# Motor_Controller.net
KiCad netlist of a schematic drawn in Altium Designer
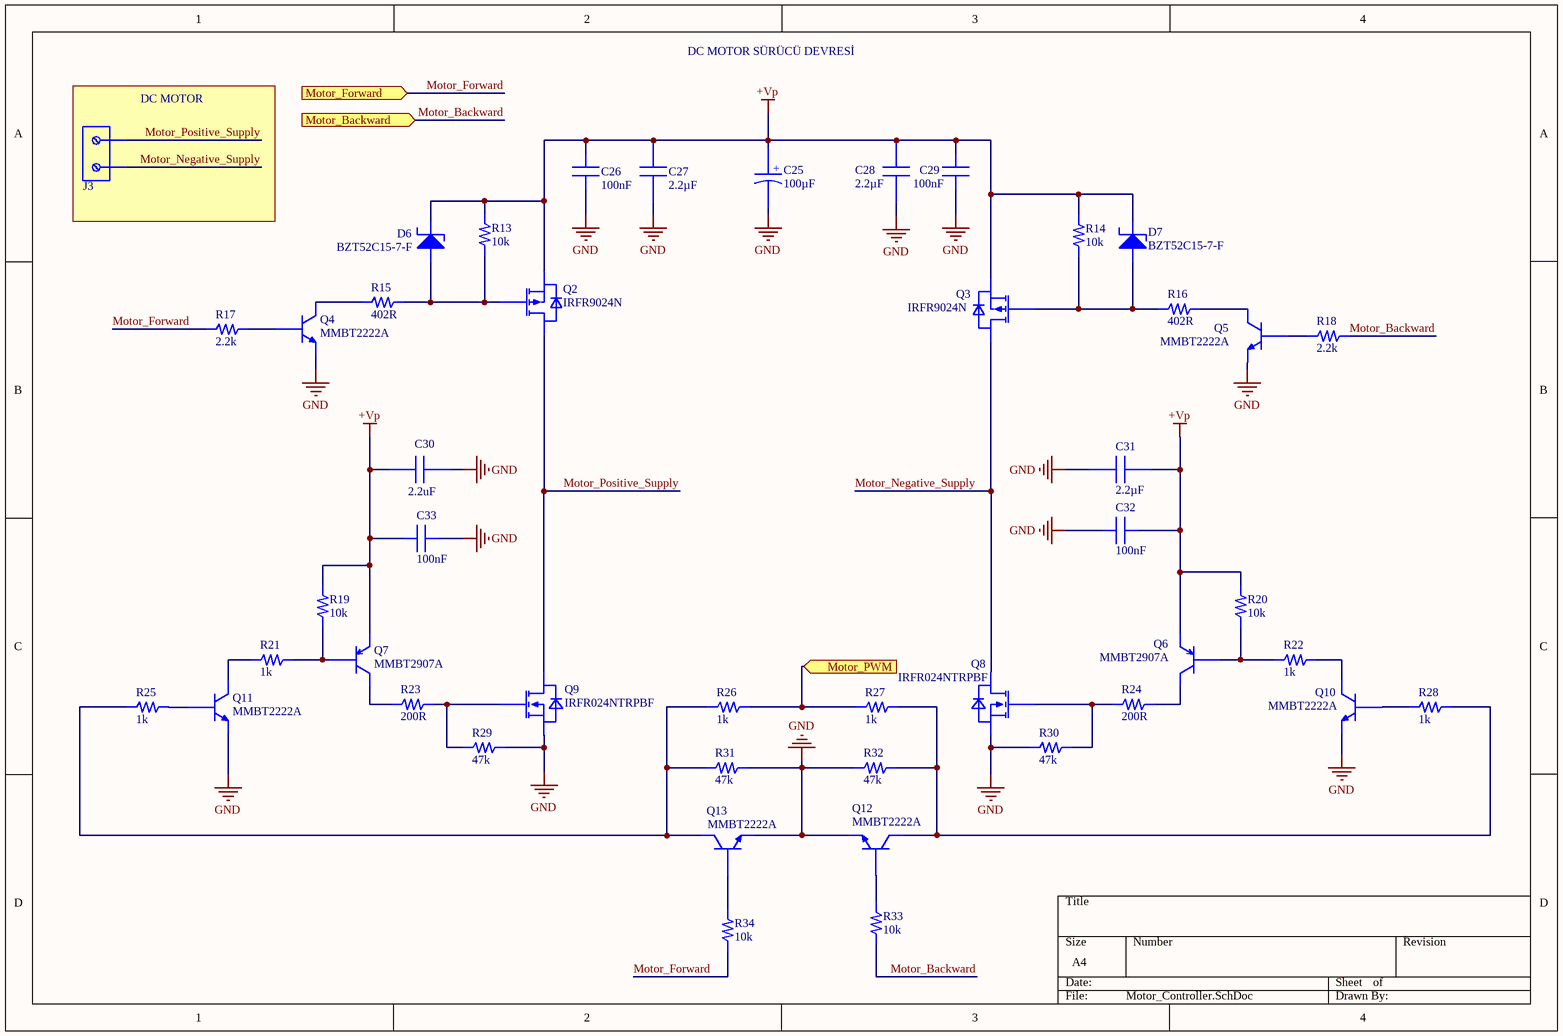
[diagram p0: Motor_Controller.SchDoc]

(export (version "E")
  (design (tool "Eeschema 10.0.6"))
  (components
    (comp (ref "C25")
      (value "100µF")
      (footprint "CAP_EEHZA1H101P")
      (description "CAP.EL.100µF 50V 10.5x10.5 105C SMD")
      (fields (field (name "MANUFACTURER") "Panasonic") (field (name "TOLERANCE") "±20 %"))
      (libsource (lib "Motor Controller SchLib") (part "CAP 100uF"))
    )
    (comp (ref "C26")
      (value "100nF")
      (footprint "CL21B104KBCNNNC")
      (description "MLCC 0805 100nF 50VDC ±10% X7R")
      (fields (field (name "TOLERANCE") "±10 %") (field (name "MANUFACTURER") "SAMSUNG"))
      (libsource (lib "Motor Controller SchLib") (part "CAP 0805 100nF"))
    )
    (comp (ref "C27")
      (value "2.2µF")
      (footprint "CAPC3216X180N")
      (description "MLCC 1206 2.2µF 50VDC ±10% X7R")
      (fields (field (name "MANUFACTURER") "SAMSUNG") (field (name "TOLERANCE") "±10 %"))
      (libsource (lib "Motor Controller SchLib") (part "CAP 1206 2.2uF"))
    )
    (comp (ref "C28")
      (value "2.2µF")
      (footprint "CAPC3216X180N")
      (description "MLCC 1206 2.2µF 50VDC ±10% X7R")
      (fields (field (name "MANUFACTURER") "SAMSUNG") (field (name "TOLERANCE") "±10 %"))
      (libsource (lib "Motor Controller SchLib") (part "CAP 1206 2.2uF"))
    )
    (comp (ref "C29")
      (value "100nF")
      (footprint "CL21B104KBCNNNC")
      (description "MLCC 0805 100nF 50VDC ±10% X7R")
      (fields (field (name "TOLERANCE") "±10 %") (field (name "MANUFACTURER") "SAMSUNG"))
      (libsource (lib "Motor Controller SchLib") (part "CAP 0805 100nF"))
    )
    (comp (ref "C30")
      (value "2.2µF")
      (footprint "CAPC3216X180N")
      (description "MLCC 1206 2.2µF 50VDC ±10% X7R")
      (fields (field (name "MANUFACTURER") "SAMSUNG") (field (name "TOLERANCE") "±10 %"))
      (libsource (lib "Motor Controller SchLib") (part "CAP 1206 2.2uF"))
    )
    (comp (ref "C31")
      (value "2.2µF")
      (footprint "CAPC3216X180N")
      (description "MLCC 1206 2.2µF 50VDC ±10% X7R")
      (fields (field (name "MANUFACTURER") "SAMSUNG") (field (name "TOLERANCE") "±10 %"))
      (libsource (lib "Motor Controller SchLib") (part "CAP 1206 2.2uF"))
    )
    (comp (ref "C32")
      (value "100nF")
      (footprint "CL21B104KBCNNNC")
      (description "MLCC 0805 100nF 50VDC ±10% X7R")
      (fields (field (name "TOLERANCE") "±10 %") (field (name "MANUFACTURER") "SAMSUNG"))
      (libsource (lib "Motor Controller SchLib") (part "CAP 0805 100nF"))
    )
    (comp (ref "C33")
      (value "100nF")
      (footprint "CL21B104KBCNNNC")
      (description "MLCC 0805 100nF 50VDC ±10% X7R")
      (fields (field (name "TOLERANCE") "±10 %") (field (name "MANUFACTURER") "SAMSUNG"))
      (libsource (lib "Motor Controller SchLib") (part "CAP 0805 100nF"))
    )
    (comp (ref "D6")
      (value "BZT52C15-7-F")
      (footprint "DIODE ZENER BZT52C15-7-F")
      (description "DIODE ZENER 500mW 15V ±5% SOD123 SMT")
      (fields (field (name "TOLERANCE") "±5 %") (field (name "POWER") "500 mW"))
      (libsource (lib "Motor Controller SchLib") (part "DIODE ZENER 15V BZT52C15-7-F"))
    )
    (comp (ref "D7")
      (value "BZT52C15-7-F")
      (footprint "DIODE ZENER BZT52C15-7-F")
      (description "DIODE ZENER 500mW 15V ±5% SOD123 SMT")
      (fields (field (name "TOLERANCE") "±5 %") (field (name "POWER") "500 mW"))
      (libsource (lib "Motor Controller SchLib") (part "DIODE ZENER 15V BZT52C15-7-F"))
    )
    (comp (ref "J3")
      (value "2x1 5mm T.B.")
      (footprint "Terminal Block 2x1")
      (description "TERM.BLK.5.00MM 2P PCB TYPE 0 BOY BLUE")
      (fields (field (name "MANUFACTURER") "DEGSON"))
      (libsource (lib "Motor Controller SchLib") (part "Terminal Block 2x1"))
    )
    (comp (ref "Q2")
      (value "IRFR9024N")
      (footprint "TO252 (DPAK) IRFR024NTRPBF")
      (description "MOSFET DIS.11A 55V P-CH TO252(DPAK) HEXFET SMT")
      (fields (field (name "POWER") "38 W") (field (name "VOLTAGE") "55 V"))
      (libsource (lib "Motor Controller SchLib") (part "P Channel Mosfet IRFR9024N"))
    )
    (comp (ref "Q3")
      (value "IRFR9024N")
      (footprint "TO252 (DPAK) IRFR024NTRPBF")
      (description "MOSFET DIS.11A 55V P-CH TO252(DPAK) HEXFET SMT")
      (fields (field (name "POWER") "38 W") (field (name "VOLTAGE") "55 V"))
      (libsource (lib "Motor Controller SchLib") (part "P Channel Mosfet IRFR9024N"))
    )
    (comp (ref "Q4")
      (value "MMBT2222A")
      (footprint "SOT23-3 MMBT2222A-HT")
      (description "TRANSISTOR DIS.600mA 40V NPN SOT23 EPITAXIAL SMT")
      (fields (field (name "MANUFACTURER") "HOTTECH") (field (name "POWER") "250 mW"))
      (libsource (lib "Motor Controller SchLib") (part "NPN Transistor MMBT2222A-HT"))
    )
    (comp (ref "Q5")
      (value "MMBT2222A")
      (footprint "SOT23-3 MMBT2222A-HT")
      (description "TRANSISTOR DIS.600mA 40V NPN SOT23 EPITAXIAL SMT")
      (fields (field (name "MANUFACTURER") "HOTTECH") (field (name "POWER") "250 mW"))
      (libsource (lib "Motor Controller SchLib") (part "NPN Transistor MMBT2222A-HT"))
    )
    (comp (ref "Q6")
      (value "MMBT2907A")
      (footprint "TRANS_MMBT2907A")
      (description "TRANSISTOR DIS.600mA 60V PNP SOT23 GEN. SMT")
      (fields (field (name "MANUFACTURER") "PANJIT") (field (name "POWER") "225 mW"))
      (libsource (lib "Motor Controller SchLib") (part "PNP Transistor MMBT2907A"))
    )
    (comp (ref "Q7")
      (value "MMBT2907A")
      (footprint "TRANS_MMBT2907A")
      (description "TRANSISTOR DIS.600mA 60V PNP SOT23 GEN. SMT")
      (fields (field (name "MANUFACTURER") "PANJIT") (field (name "POWER") "225 mW"))
      (libsource (lib "Motor Controller SchLib") (part "PNP Transistor MMBT2907A"))
    )
    (comp (ref "Q8")
      (value "IRFR024NTRPBF")
      (footprint "TO252 (DPAK) IRFR024NTRPBF")
      (description "MOSFET DIS.17A 55V N-CH TO252(DPAK) HEXFET SMT")
      (fields (field (name "VOLTAGE") "55 V") (field (name "POWER") "45W"))
      (libsource (lib "Motor Controller SchLib") (part "N Channel Mosfet IRFR024NTRPBF"))
    )
    (comp (ref "Q9")
      (value "IRFR024NTRPBF")
      (footprint "TO252 (DPAK) IRFR024NTRPBF")
      (description "MOSFET DIS.17A 55V N-CH TO252(DPAK) HEXFET SMT")
      (fields (field (name "VOLTAGE") "55 V") (field (name "POWER") "45W"))
      (libsource (lib "Motor Controller SchLib") (part "N Channel Mosfet IRFR024NTRPBF"))
    )
    (comp (ref "Q10")
      (value "MMBT2222A")
      (footprint "SOT23-3 MMBT2222A-HT")
      (description "TRANSISTOR DIS.600mA 40V NPN SOT23 EPITAXIAL SMT")
      (fields (field (name "MANUFACTURER") "HOTTECH") (field (name "POWER") "250 mW"))
      (libsource (lib "Motor Controller SchLib") (part "NPN Transistor MMBT2222A-HT"))
    )
    (comp (ref "Q11")
      (value "MMBT2222A")
      (footprint "SOT23-3 MMBT2222A-HT")
      (description "TRANSISTOR DIS.600mA 40V NPN SOT23 EPITAXIAL SMT")
      (fields (field (name "MANUFACTURER") "HOTTECH") (field (name "POWER") "250 mW"))
      (libsource (lib "Motor Controller SchLib") (part "NPN Transistor MMBT2222A-HT"))
    )
    (comp (ref "Q12")
      (value "MMBT2222A")
      (footprint "SOT23-3 MMBT2222A-HT")
      (description "TRANSISTOR DIS.600mA 40V NPN SOT23 EPITAXIAL SMT")
      (fields (field (name "POWER") "250 mW") (field (name "MANUFACTURER") "HOTTECH"))
      (libsource (lib "Motor Controller SchLib") (part "NPN Transistor MMBT2222A-HT"))
    )
    (comp (ref "Q13")
      (value "MMBT2222A")
      (footprint "SOT23-3 MMBT2222A-HT")
      (description "TRANSISTOR DIS.600mA 40V NPN SOT23 EPITAXIAL SMT")
      (fields (field (name "POWER") "250 mW") (field (name "MANUFACTURER") "HOTTECH"))
      (libsource (lib "Motor Controller SchLib") (part "NPN Transistor MMBT2222A-HT"))
    )
    (comp (ref "R13")
      (value "10k")
      (footprint "RES 0402 ROYALOHM GENERAL")
      (description "RES.(1005) 0402 10K Ohms 5% 1/16W 100PPM 0402WGJ0103TCE")
      (fields (field (name "TOLERANCE") "%5") (field (name "MANUFACTURER") "ROYALOHM"))
      (libsource (lib "Motor Controller SchLib") (part "RES 0402 10k"))
    )
    (comp (ref "R14")
      (value "10k")
      (footprint "RES 0402 ROYALOHM GENERAL")
      (description "RES.(1005) 0402 10K Ohms 5% 1/16W 100PPM 0402WGJ0103TCE")
      (fields (field (name "TOLERANCE") "%5") (field (name "MANUFACTURER") "ROYALOHM"))
      (libsource (lib "Motor Controller SchLib") (part "RES 0402 10k"))
    )
    (comp (ref "R15")
      (value "402R")
      (footprint "CHIP RES 0805 1k")
      (description "RES.(2012) 0805 402 Ohms 1% 1/8W-S 100PPM 0805S8F4020T5E")
      (fields (field (name "MANUFACTURER") "ROYALOHM") (field (name "TOLERANCE") "±1 %"))
      (libsource (lib "Motor Controller SchLib") (part "RES 0805 402 Ohms 0402WGF4020TCE"))
    )
    (comp (ref "R16")
      (value "402R")
      (footprint "CHIP RES 0805 1k")
      (description "RES.(2012) 0805 402 Ohms 1% 1/8W-S 100PPM 0805S8F4020T5E")
      (fields (field (name "MANUFACTURER") "ROYALOHM") (field (name "TOLERANCE") "±1 %"))
      (libsource (lib "Motor Controller SchLib") (part "RES 0805 402 Ohms 0402WGF4020TCE"))
    )
    (comp (ref "R17")
      (value "2.2k")
      (footprint "RES 0402 ROYALOHM GENERAL")
      (description "RES. 0805 2.2k Ohms 1% 1/8W-S 100PPM 0402WGF2201TCE")
      (fields (field (name "TOLERANCE") "%1") (field (name "POWER") "1/16 W"))
      (libsource (lib "Motor Controller SchLib") (part "RES 0402 2.2k 0402WGF2201TCE"))
    )
    (comp (ref "R18")
      (value "2.2k")
      (footprint "RES 0402 ROYALOHM GENERAL")
      (description "RES. 0805 2.2k Ohms 1% 1/8W-S 100PPM 0402WGF2201TCE")
      (fields (field (name "TOLERANCE") "%1") (field (name "POWER") "1/16 W"))
      (libsource (lib "Motor Controller SchLib") (part "RES 0402 2.2k 0402WGF2201TCE"))
    )
    (comp (ref "R19")
      (value "10k")
      (footprint "RES 0402 ROYALOHM GENERAL")
      (description "RES.(1005) 0402 10K Ohms 5% 1/16W 100PPM 0402WGJ0103TCE")
      (fields (field (name "TOLERANCE") "%5") (field (name "MANUFACTURER") "ROYALOHM"))
      (libsource (lib "Motor Controller SchLib") (part "RES 0402 10k"))
    )
    (comp (ref "R20")
      (value "10k")
      (footprint "RES 0402 ROYALOHM GENERAL")
      (description "RES.(1005) 0402 10K Ohms 5% 1/16W 100PPM 0402WGJ0103TCE")
      (fields (field (name "TOLERANCE") "%5") (field (name "MANUFACTURER") "ROYALOHM"))
      (libsource (lib "Motor Controller SchLib") (part "RES 0402 10k"))
    )
    (comp (ref "R21")
      (value "1k")
      (footprint "RES 0402 ROYALOHM GENERAL")
      (description "RES.(1005) 0402 1K Ohms 1% 1/10W\r\nHP02WAF1001TCE")
      (fields (field (name "MANUFACTURER") "ROYALOHM") (field (name "TOLERANCE") "±1 %"))
      (libsource (lib "Motor Controller SchLib") (part "RES 0402 1k HP02WAF1001TCE"))
    )
    (comp (ref "R22")
      (value "1k")
      (footprint "RES 0402 ROYALOHM GENERAL")
      (description "RES.(1005) 0402 1K Ohms 1% 1/10W\r\nHP02WAF1001TCE")
      (fields (field (name "MANUFACTURER") "ROYALOHM") (field (name "TOLERANCE") "±1 %"))
      (libsource (lib "Motor Controller SchLib") (part "RES 0402 1k HP02WAF1001TCE"))
    )
    (comp (ref "R23")
      (value "200R")
      (footprint "CHIP RES 0805 1k")
      (description "RES.(2012) 0805 200 Ohms 5% 1/8W-S 100PPM\r\n0805S8J0201T5E")
      (fields (field (name "TOLERANCE") "±5 %") (field (name "MANUFACTURER") "ROYALOHM"))
      (libsource (lib "Motor Controller SchLib") (part "RES 0805 200Ohms 0805S8J0201T5E"))
    )
    (comp (ref "R24")
      (value "200R")
      (footprint "CHIP RES 0805 1k")
      (description "RES.(2012) 0805 200 Ohms 5% 1/8W-S 100PPM\r\n0805S8J0201T5E")
      (fields (field (name "TOLERANCE") "±5 %") (field (name "MANUFACTURER") "ROYALOHM"))
      (libsource (lib "Motor Controller SchLib") (part "RES 0805 200Ohms 0805S8J0201T5E"))
    )
    (comp (ref "R25")
      (value "1k")
      (footprint "RES 0402 ROYALOHM GENERAL")
      (description "RES.(1005) 0402 1K Ohms 1% 1/10W\r\nHP02WAF1001TCE")
      (fields (field (name "MANUFACTURER") "ROYALOHM") (field (name "TOLERANCE") "±1 %"))
      (libsource (lib "Motor Controller SchLib") (part "RES 0402 1k HP02WAF1001TCE"))
    )
    (comp (ref "R26")
      (value "1k")
      (footprint "RES 0402 ROYALOHM GENERAL")
      (description "RES.(1005) 0402 1K Ohms 1% 1/10W\r\nHP02WAF1001TCE")
      (fields (field (name "MANUFACTURER") "ROYALOHM") (field (name "TOLERANCE") "±1 %"))
      (libsource (lib "Motor Controller SchLib") (part "RES 0402 1k HP02WAF1001TCE"))
    )
    (comp (ref "R27")
      (value "1k")
      (footprint "RES 0402 ROYALOHM GENERAL")
      (description "RES.(1005) 0402 1K Ohms 1% 1/10W\r\nHP02WAF1001TCE")
      (fields (field (name "MANUFACTURER") "ROYALOHM") (field (name "TOLERANCE") "±1 %"))
      (libsource (lib "Motor Controller SchLib") (part "RES 0402 1k HP02WAF1001TCE"))
    )
    (comp (ref "R28")
      (value "1k")
      (footprint "RES 0402 ROYALOHM GENERAL")
      (description "RES.(1005) 0402 1K Ohms 1% 1/10W\r\nHP02WAF1001TCE")
      (fields (field (name "MANUFACTURER") "ROYALOHM") (field (name "TOLERANCE") "±1 %"))
      (libsource (lib "Motor Controller SchLib") (part "RES 0402 1k HP02WAF1001TCE"))
    )
    (comp (ref "R29")
      (value "47k")
      (footprint "RES 0402 ROYALOHM GENERAL")
      (description "RES.(1005) 0402 47K Ohms 1% 1/10W\r\nHP02WAF4702TCE")
      (fields (field (name "TOLERANCE") "±1 %") (field (name "MANUFACTURER") "ROYALOHM"))
      (libsource (lib "Motor Controller SchLib") (part "RES 0402 47k HP02WAF4702TCE"))
    )
    (comp (ref "R30")
      (value "47k")
      (footprint "RES 0402 ROYALOHM GENERAL")
      (description "RES.(1005) 0402 47K Ohms 1% 1/10W\r\nHP02WAF4702TCE")
      (fields (field (name "TOLERANCE") "±1 %") (field (name "MANUFACTURER") "ROYALOHM"))
      (libsource (lib "Motor Controller SchLib") (part "RES 0402 47k HP02WAF4702TCE"))
    )
    (comp (ref "R31")
      (value "47k")
      (footprint "RES 0402 ROYALOHM GENERAL")
      (description "RES.(1005) 0402 47K Ohms 1% 1/10W\r\nHP02WAF4702TCE")
      (fields (field (name "TOLERANCE") "±1 %") (field (name "MANUFACTURER") "ROYALOHM"))
      (libsource (lib "Motor Controller SchLib") (part "RES 0402 47k HP02WAF4702TCE"))
    )
    (comp (ref "R32")
      (value "47k")
      (footprint "RES 0402 ROYALOHM GENERAL")
      (description "RES.(1005) 0402 47K Ohms 1% 1/10W\r\nHP02WAF4702TCE")
      (fields (field (name "TOLERANCE") "±1 %") (field (name "MANUFACTURER") "ROYALOHM"))
      (libsource (lib "Motor Controller SchLib") (part "RES 0402 47k HP02WAF4702TCE"))
    )
    (comp (ref "R33")
      (value "10k")
      (footprint "RES 0402 ROYALOHM GENERAL")
      (description "RES.(1005) 0402 10K Ohms 5% 1/16W 100PPM 0402WGJ0103TCE")
      (fields (field (name "TOLERANCE") "%5") (field (name "MANUFACTURER") "ROYALOHM"))
      (libsource (lib "Motor Controller SchLib") (part "RES 0402 10k"))
    )
    (comp (ref "R34")
      (value "10k")
      (footprint "RES 0402 ROYALOHM GENERAL")
      (description "RES.(1005) 0402 10K Ohms 5% 1/16W 100PPM 0402WGJ0103TCE")
      (fields (field (name "TOLERANCE") "%5") (field (name "MANUFACTURER") "ROYALOHM"))
      (libsource (lib "Motor Controller SchLib") (part "RES 0402 10k"))
    )
  )
  (nets
    (net (code "1") (name "+Vp") (class "Default")
      (node (ref "C25") (pin "1") (pinfunction "1_1") (pintype "passive"))
      (node (ref "C26") (pin "2") (pinfunction "2_2") (pintype "passive"))
      (node (ref "C27") (pin "2") (pinfunction "2_2") (pintype "passive"))
      (node (ref "C28") (pin "2") (pinfunction "2_2") (pintype "passive"))
      (node (ref "C29") (pin "2") (pinfunction "2_2") (pintype "passive"))
      (node (ref "C30") (pin "1") (pinfunction "1_1") (pintype "passive"))
      (node (ref "C31") (pin "2") (pinfunction "2_2") (pintype "passive"))
      (node (ref "C32") (pin "2") (pinfunction "2_2") (pintype "passive"))
      (node (ref "C33") (pin "1") (pinfunction "1_1") (pintype "passive"))
      (node (ref "D6") (pin "2") (pinfunction "Cathode_2") (pintype "passive"))
      (node (ref "D7") (pin "2") (pinfunction "Cathode_2") (pintype "passive"))
      (node (ref "Q2") (pin "3") (pinfunction "Source_3") (pintype "passive"))
      (node (ref "Q3") (pin "3") (pinfunction "Source_3") (pintype "passive"))
      (node (ref "Q6") (pin "2") (pinfunction "Emitter_2") (pintype "passive"))
      (node (ref "Q7") (pin "2") (pinfunction "Emitter_2") (pintype "passive"))
      (node (ref "R13") (pin "2") (pinfunction "2_2") (pintype "passive"))
      (node (ref "R14") (pin "2") (pinfunction "2_2") (pintype "passive"))
      (node (ref "R19") (pin "2") (pinfunction "2_2") (pintype "passive"))
      (node (ref "R20") (pin "2") (pinfunction "2_2") (pintype "passive"))
    )
    (net (code "2") (name "/Motor_Backward") (class "Default")
      (node (ref "R18") (pin "2") (pinfunction "2_2") (pintype "passive"))
      (node (ref "R33") (pin "1") (pinfunction "1_1") (pintype "passive"))
    )
    (net (code "3") (name "/Motor_Forward") (class "Default")
      (node (ref "R17") (pin "1") (pinfunction "1_1") (pintype "passive"))
      (node (ref "R34") (pin "1") (pinfunction "1_1") (pintype "passive"))
    )
    (net (code "4") (name "/Motor_Negative_Supply") (class "Default")
      (node (ref "J3") (pin "2") (pinfunction "2_2") (pintype "power_in"))
      (node (ref "Q3") (pin "4") (pinfunction "Drain_4") (pintype "passive"))
      (node (ref "Q8") (pin "4") (pinfunction "Drain_4") (pintype "passive"))
    )
    (net (code "5") (name "/Motor_PWM") (class "Default")
      (node (ref "R26") (pin "2") (pinfunction "2_2") (pintype "passive"))
      (node (ref "R27") (pin "1") (pinfunction "1_1") (pintype "passive"))
    )
    (net (code "6") (name "/Motor_Positive_Supply") (class "Default")
      (node (ref "J3") (pin "1") (pinfunction "1_1") (pintype "power_in"))
      (node (ref "Q2") (pin "4") (pinfunction "Drain_4") (pintype "passive"))
      (node (ref "Q9") (pin "4") (pinfunction "Drain_4") (pintype "passive"))
    )
    (net (code "7") (name "GND") (class "Default")
      (node (ref "C25") (pin "2") (pinfunction "2_2") (pintype "passive"))
      (node (ref "C26") (pin "1") (pinfunction "1_1") (pintype "passive"))
      (node (ref "C27") (pin "1") (pinfunction "1_1") (pintype "passive"))
      (node (ref "C28") (pin "1") (pinfunction "1_1") (pintype "passive"))
      (node (ref "C29") (pin "1") (pinfunction "1_1") (pintype "passive"))
      (node (ref "C30") (pin "2") (pinfunction "2_2") (pintype "passive"))
      (node (ref "C31") (pin "1") (pinfunction "1_1") (pintype "passive"))
      (node (ref "C32") (pin "1") (pinfunction "1_1") (pintype "passive"))
      (node (ref "C33") (pin "2") (pinfunction "2_2") (pintype "passive"))
      (node (ref "Q10") (pin "2") (pinfunction "Emitter_2") (pintype "passive"))
      (node (ref "Q11") (pin "2") (pinfunction "Emitter_2") (pintype "passive"))
      (node (ref "Q12") (pin "2") (pinfunction "Emitter_2") (pintype "passive"))
      (node (ref "Q13") (pin "2") (pinfunction "Emitter_2") (pintype "passive"))
      (node (ref "Q4") (pin "2") (pinfunction "Emitter_2") (pintype "passive"))
      (node (ref "Q5") (pin "2") (pinfunction "Emitter_2") (pintype "passive"))
      (node (ref "Q8") (pin "3") (pinfunction "Source_3") (pintype "passive"))
      (node (ref "Q9") (pin "3") (pinfunction "Source_3") (pintype "passive"))
      (node (ref "R29") (pin "2") (pinfunction "2_2") (pintype "passive"))
      (node (ref "R30") (pin "1") (pinfunction "1_1") (pintype "passive"))
      (node (ref "R31") (pin "2") (pinfunction "2_2") (pintype "passive"))
      (node (ref "R32") (pin "1") (pinfunction "1_1") (pintype "passive"))
    )
    (net (code "8") (name "Net-(D6-Anode)") (class "Default")
      (node (ref "D6") (pin "1") (pinfunction "Anode_1") (pintype "passive"))
      (node (ref "Q2") (pin "1") (pinfunction "Gate_1") (pintype "passive"))
      (node (ref "R13") (pin "1") (pinfunction "1_1") (pintype "passive"))
      (node (ref "R15") (pin "2") (pinfunction "2_2") (pintype "passive"))
    )
    (net (code "9") (name "Net-(D7-Anode)") (class "Default")
      (node (ref "D7") (pin "1") (pinfunction "Anode_1") (pintype "passive"))
      (node (ref "Q3") (pin "1") (pinfunction "Gate_1") (pintype "passive"))
      (node (ref "R14") (pin "1") (pinfunction "1_1") (pintype "passive"))
      (node (ref "R16") (pin "1") (pinfunction "1_1") (pintype "passive"))
    )
    (net (code "10") (name "Net-(Q4-Base)") (class "Default")
      (node (ref "Q4") (pin "1") (pinfunction "Base_1") (pintype "passive"))
      (node (ref "R17") (pin "2") (pinfunction "2_2") (pintype "passive"))
    )
    (net (code "11") (name "Net-(Q4-Collector)") (class "Default")
      (node (ref "Q4") (pin "3") (pinfunction "Collector_3") (pintype "passive"))
      (node (ref "R15") (pin "1") (pinfunction "1_1") (pintype "passive"))
    )
    (net (code "12") (name "Net-(Q5-Base)") (class "Default")
      (node (ref "Q5") (pin "1") (pinfunction "Base_1") (pintype "passive"))
      (node (ref "R18") (pin "1") (pinfunction "1_1") (pintype "passive"))
    )
    (net (code "13") (name "Net-(Q5-Collector)") (class "Default")
      (node (ref "Q5") (pin "3") (pinfunction "Collector_3") (pintype "passive"))
      (node (ref "R16") (pin "2") (pinfunction "2_2") (pintype "passive"))
    )
    (net (code "14") (name "Net-(Q6-Base)") (class "Default")
      (node (ref "Q6") (pin "1") (pinfunction "Base_1") (pintype "passive"))
      (node (ref "R20") (pin "1") (pinfunction "1_1") (pintype "passive"))
      (node (ref "R22") (pin "1") (pinfunction "1_1") (pintype "passive"))
    )
    (net (code "15") (name "Net-(Q6-Collector)") (class "Default")
      (node (ref "Q6") (pin "3") (pinfunction "Collector_3") (pintype "passive"))
      (node (ref "R24") (pin "2") (pinfunction "2_2") (pintype "passive"))
    )
    (net (code "16") (name "Net-(Q7-Base)") (class "Default")
      (node (ref "Q7") (pin "1") (pinfunction "Base_1") (pintype "passive"))
      (node (ref "R19") (pin "1") (pinfunction "1_1") (pintype "passive"))
      (node (ref "R21") (pin "2") (pinfunction "2_2") (pintype "passive"))
    )
    (net (code "17") (name "Net-(Q7-Collector)") (class "Default")
      (node (ref "Q7") (pin "3") (pinfunction "Collector_3") (pintype "passive"))
      (node (ref "R23") (pin "1") (pinfunction "1_1") (pintype "passive"))
    )
    (net (code "18") (name "Net-(Q8-Gate)") (class "Default")
      (node (ref "Q8") (pin "1") (pinfunction "Gate_1") (pintype "passive"))
      (node (ref "R24") (pin "1") (pinfunction "1_1") (pintype "passive"))
      (node (ref "R30") (pin "2") (pinfunction "2_2") (pintype "passive"))
    )
    (net (code "19") (name "Net-(Q9-Gate)") (class "Default")
      (node (ref "Q9") (pin "1") (pinfunction "Gate_1") (pintype "passive"))
      (node (ref "R23") (pin "2") (pinfunction "2_2") (pintype "passive"))
      (node (ref "R29") (pin "1") (pinfunction "1_1") (pintype "passive"))
    )
    (net (code "20") (name "Net-(Q10-Base)") (class "Default")
      (node (ref "Q10") (pin "1") (pinfunction "Base_1") (pintype "passive"))
      (node (ref "R28") (pin "1") (pinfunction "1_1") (pintype "passive"))
    )
    (net (code "21") (name "Net-(Q10-Collector)") (class "Default")
      (node (ref "Q10") (pin "3") (pinfunction "Collector_3") (pintype "passive"))
      (node (ref "R22") (pin "2") (pinfunction "2_2") (pintype "passive"))
    )
    (net (code "22") (name "Net-(Q11-Base)") (class "Default")
      (node (ref "Q11") (pin "1") (pinfunction "Base_1") (pintype "passive"))
      (node (ref "R25") (pin "2") (pinfunction "2_2") (pintype "passive"))
    )
    (net (code "23") (name "Net-(Q11-Collector)") (class "Default")
      (node (ref "Q11") (pin "3") (pinfunction "Collector_3") (pintype "passive"))
      (node (ref "R21") (pin "1") (pinfunction "1_1") (pintype "passive"))
    )
    (net (code "24") (name "Net-(Q12-Base)") (class "Default")
      (node (ref "Q12") (pin "1") (pinfunction "Base_1") (pintype "passive"))
      (node (ref "R33") (pin "2") (pinfunction "2_2") (pintype "passive"))
    )
    (net (code "25") (name "Net-(Q12-Collector)") (class "Default")
      (node (ref "Q12") (pin "3") (pinfunction "Collector_3") (pintype "passive"))
      (node (ref "R27") (pin "2") (pinfunction "2_2") (pintype "passive"))
      (node (ref "R28") (pin "2") (pinfunction "2_2") (pintype "passive"))
      (node (ref "R32") (pin "2") (pinfunction "2_2") (pintype "passive"))
    )
    (net (code "26") (name "Net-(Q13-Base)") (class "Default")
      (node (ref "Q13") (pin "1") (pinfunction "Base_1") (pintype "passive"))
      (node (ref "R34") (pin "2") (pinfunction "2_2") (pintype "passive"))
    )
    (net (code "27") (name "Net-(Q13-Collector)") (class "Default")
      (node (ref "Q13") (pin "3") (pinfunction "Collector_3") (pintype "passive"))
      (node (ref "R25") (pin "1") (pinfunction "1_1") (pintype "passive"))
      (node (ref "R26") (pin "1") (pinfunction "1_1") (pintype "passive"))
      (node (ref "R31") (pin "1") (pinfunction "1_1") (pintype "passive"))
    )
  )
)
